# external_strip_v1.net
KiCad netlist of a schematic drawn in EAGLE
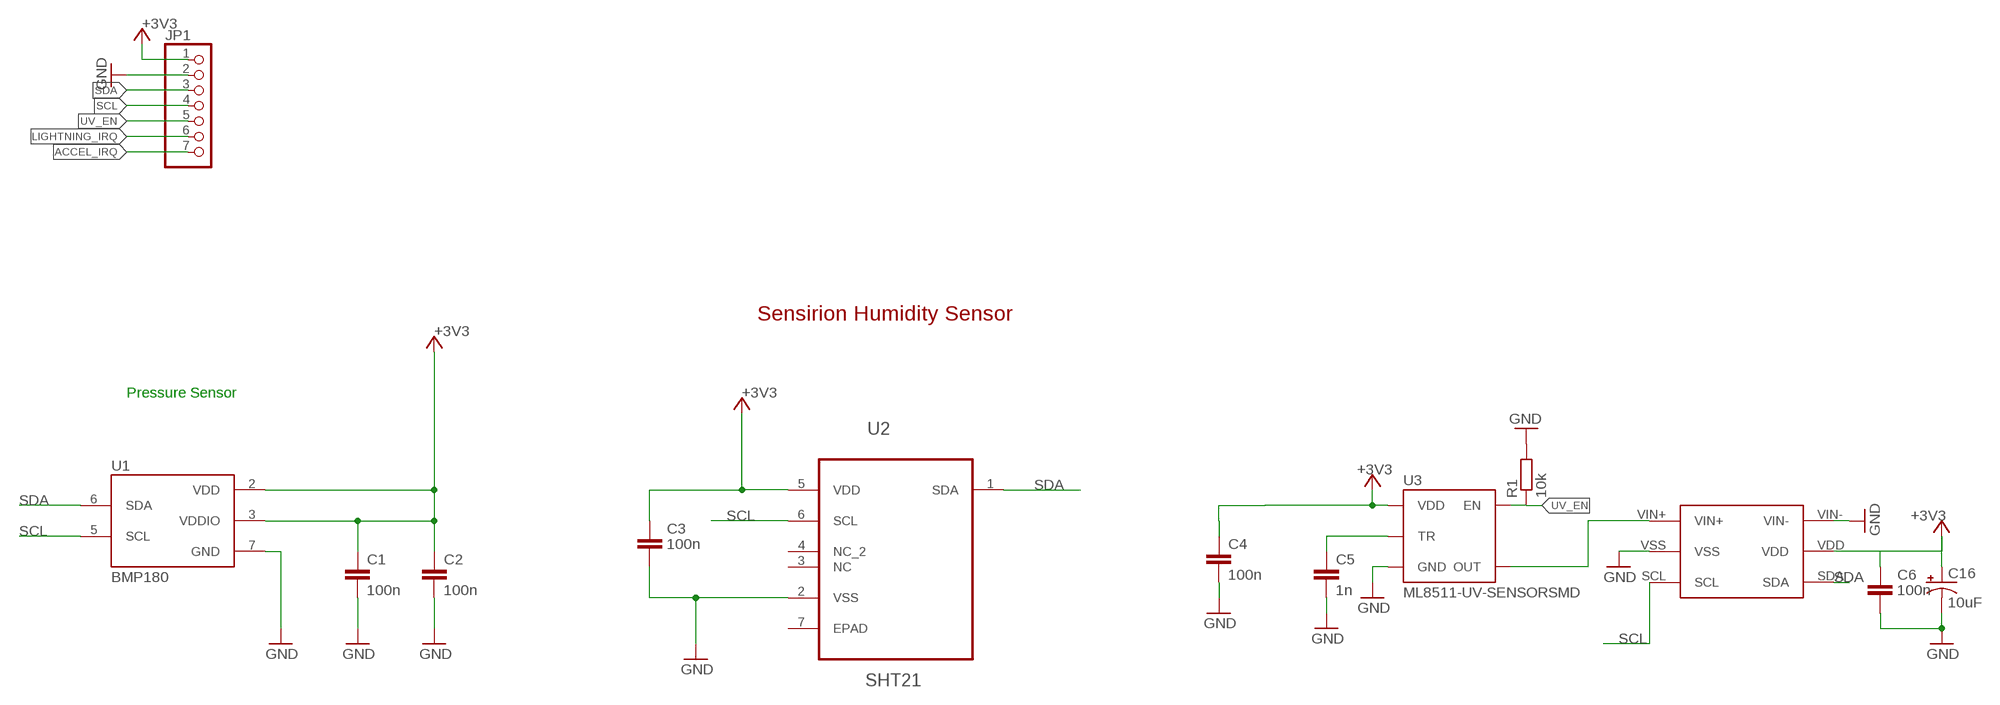
[diagram p0: schematic, sheet 1, part 1 of 2]
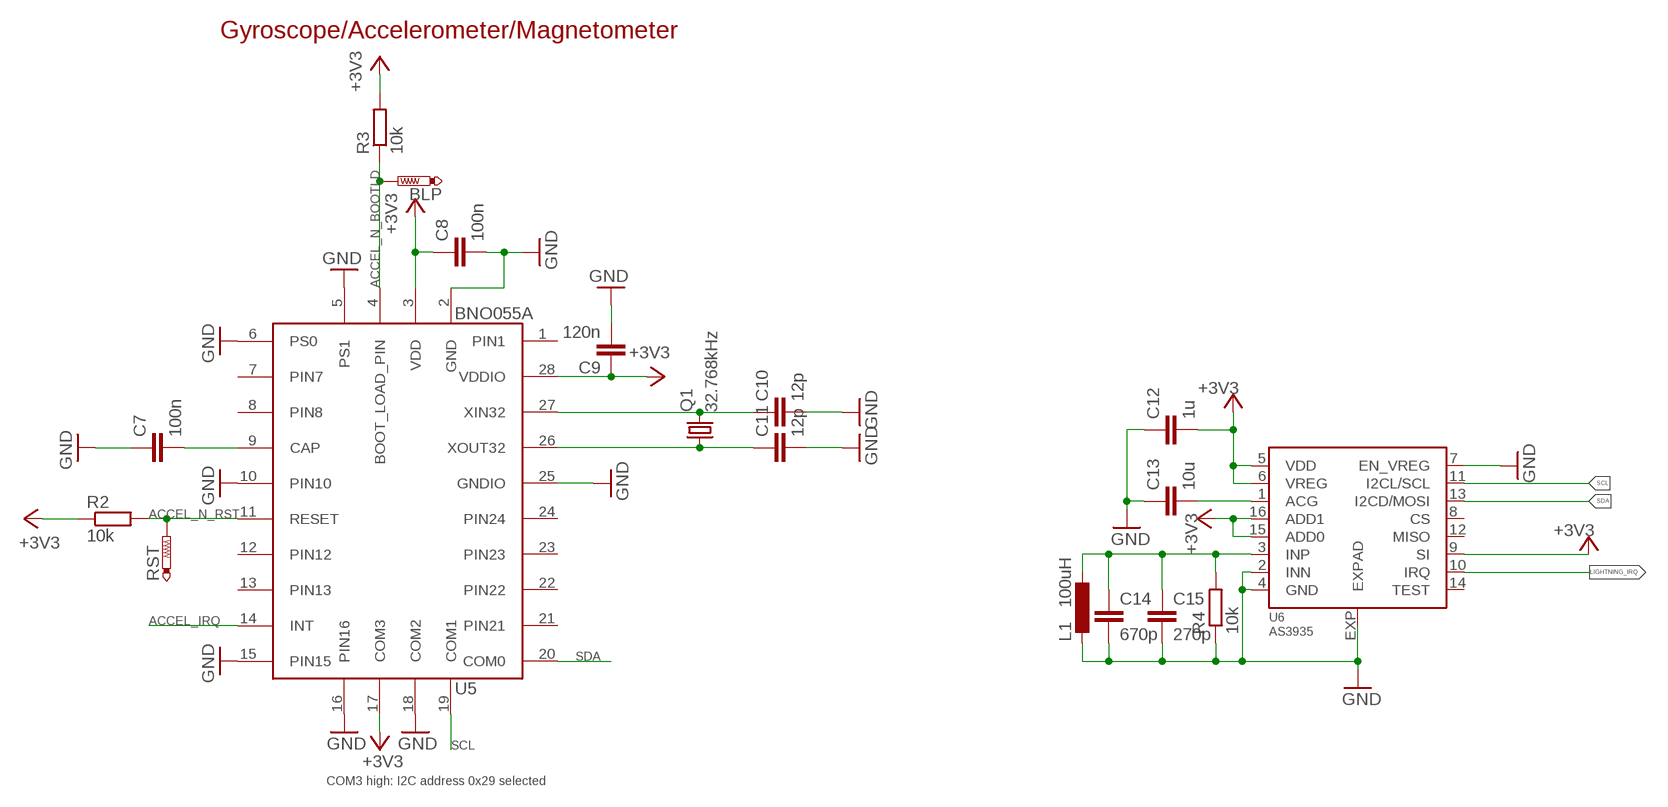
[diagram p1: schematic, sheet 1, part 2 of 2]

(export (version "E")
  (design (tool "Eeschema 10.0.6"))
  (components
    (comp (ref "BLP")
      (value "PTR1B1,27")
      (footprint "eagle-import:B1,27")
      (libsource (lib "eagle-import") (part "PTR1B1,27"))
    )
    (comp (ref "C1")
      (value "100n")
      (footprint "eagle-import:C0603")
      (libsource (lib "eagle-import") (part "C-EUC0603"))
    )
    (comp (ref "C2")
      (value "100n")
      (footprint "eagle-import:C0603")
      (libsource (lib "eagle-import") (part "C-EUC0603"))
    )
    (comp (ref "C3")
      (value "100n")
      (footprint "eagle-import:C0603")
      (libsource (lib "eagle-import") (part "C-EUC0603"))
    )
    (comp (ref "C4")
      (value "100n")
      (footprint "eagle-import:0603-CAP")
      (libsource (lib "eagle-import") (part "0.1UF-25V(+80/-20%)(0603)"))
    )
    (comp (ref "C5")
      (value "1n")
      (footprint "eagle-import:0603-CAP")
      (libsource (lib "eagle-import") (part "1NF/1000PF-50V-10%(0603)"))
    )
    (comp (ref "C6")
      (value "100n")
      (footprint "eagle-import:C0603")
      (libsource (lib "eagle-import") (part "C-EUC0603"))
    )
    (comp (ref "C7")
      (value "100n")
      (footprint "eagle-import:C0603")
      (libsource (lib "eagle-import") (part "C-EUC0603"))
    )
    (comp (ref "C8")
      (value "100n")
      (footprint "eagle-import:C0603")
      (libsource (lib "eagle-import") (part "C-EUC0603"))
    )
    (comp (ref "C9")
      (value "120n")
      (footprint "eagle-import:C0603")
      (libsource (lib "eagle-import") (part "C-EUC0603"))
    )
    (comp (ref "C10")
      (value "12p")
      (footprint "eagle-import:C0603")
      (libsource (lib "eagle-import") (part "C-EUC0603"))
    )
    (comp (ref "C11")
      (value "12p")
      (footprint "eagle-import:C0603")
      (libsource (lib "eagle-import") (part "C-EUC0603"))
    )
    (comp (ref "C12")
      (value "1u")
      (footprint "eagle-import:C0603")
      (libsource (lib "eagle-import") (part "C-EUC0603"))
    )
    (comp (ref "C13")
      (value "10u")
      (footprint "eagle-import:C0603")
      (libsource (lib "eagle-import") (part "C-EUC0603"))
    )
    (comp (ref "C14")
      (value "670p")
      (footprint "eagle-import:C0603")
      (libsource (lib "eagle-import") (part "C-EUC0603"))
    )
    (comp (ref "C15")
      (value "270p")
      (footprint "eagle-import:C0603")
      (libsource (lib "eagle-import") (part "C-EUC0603"))
    )
    (comp (ref "C16")
      (value "10uF")
      (footprint "eagle-import:EIA3216")
      (libsource (lib "eagle-import") (part "10UF-TANT"))
    )
    (comp (ref "JP1")
      (value "PINHD-1X7")
      (footprint "eagle-import:1X07")
      (libsource (lib "eagle-import") (part "PINHD-1X7"))
    )
    (comp (ref "L1")
      (value "100uH")
      (footprint "eagle-import:COILCRAFT")
      (libsource (lib "eagle-import") (part "COILCRAFT"))
    )
    (comp (ref "Q1")
      (value "32.768kHz")
      (footprint "eagle-import:FC-12M")
      (libsource (lib "eagle-import") (part "FC-12M"))
    )
    (comp (ref "R1")
      (value "10k")
      (footprint "eagle-import:R0603")
      (libsource (lib "eagle-import") (part "resistor_R-EU_R0603"))
    )
    (comp (ref "R2")
      (value "10k")
      (footprint "eagle-import:R0603")
      (libsource (lib "eagle-import") (part "R-EU_R0603"))
    )
    (comp (ref "R3")
      (value "10k")
      (footprint "eagle-import:R0603")
      (libsource (lib "eagle-import") (part "R-EU_R0603"))
    )
    (comp (ref "R4")
      (value "10k")
      (footprint "eagle-import:R0603")
      (libsource (lib "eagle-import") (part "resistor_R-EU_R0603"))
    )
    (comp (ref "RST")
      (value "PTR1B1,27")
      (footprint "eagle-import:B1,27")
      (libsource (lib "eagle-import") (part "PTR1B1,27"))
    )
    (comp (ref "U1")
      (value "BMP180")
      (footprint "eagle-import:BMP180")
      (libsource (lib "eagle-import") (part "BMP180"))
    )
    (comp (ref "U2")
      (value "SHT21")
      (footprint "eagle-import:DFN300X300X110-7N")
      (libsource (lib "eagle-import") (part "SHT21"))
    )
    (comp (ref "U3")
      (value "ML8511-UV-SENSORSMD")
      (footprint "eagle-import:ML8511")
      (libsource (lib "eagle-import") (part "ML8511-UV-SENSORSMD"))
    )
    (comp (ref "U4")
      (value "MCP3425")
      (footprint "eagle-import:SOT-23-6")
      (libsource (lib "eagle-import") (part "MCP3425"))
    )
    (comp (ref "U5")
      (value "BNO055A")
      (footprint "eagle-import:BNO055")
      (libsource (lib "eagle-import") (part "BNO055A"))
    )
    (comp (ref "U6")
      (value "AS3935")
      (footprint "eagle-import:16LDMLPQ")
      (libsource (lib "eagle-import") (part "AS3935"))
    )
  )
  (nets
    (net (code "1") (name "+3V3") (class "Default")
      (node (ref "C1") (pin "1") (pinfunction "1_1") (pintype "passive"))
      (node (ref "C12") (pin "2") (pinfunction "2_2") (pintype "passive"))
      (node (ref "C16") (pin "A") (pinfunction "+_A") (pintype "passive"))
      (node (ref "C2") (pin "1") (pinfunction "1_1") (pintype "passive"))
      (node (ref "C3") (pin "1") (pinfunction "1_1") (pintype "passive"))
      (node (ref "C4") (pin "1") (pinfunction "1_1") (pintype "passive"))
      (node (ref "C6") (pin "1") (pinfunction "1_1") (pintype "passive"))
      (node (ref "C8") (pin "1") (pinfunction "1_1") (pintype "passive"))
      (node (ref "C9") (pin "1") (pinfunction "1_1") (pintype "passive"))
      (node (ref "JP1") (pin "1") (pinfunction "1_1") (pintype "passive"))
      (node (ref "R2") (pin "1") (pinfunction "1_1") (pintype "passive"))
      (node (ref "R3") (pin "2") (pinfunction "2_2") (pintype "passive"))
      (node (ref "U1") (pin "2") (pinfunction "VDD_2") (pintype "power_in"))
      (node (ref "U1") (pin "3") (pinfunction "VDDIO_3") (pintype "power_in"))
      (node (ref "U2") (pin "5") (pinfunction "VDD_5") (pintype "power_in"))
      (node (ref "U3") (pin "7") (pinfunction "VDD_7") (pintype "power_in"))
      (node (ref "U4") (pin "VDD") (pinfunction "VDD_VDD") (pintype "bidirectional"))
      (node (ref "U5") (pin "17") (pinfunction "COM3_17") (pintype "bidirectional"))
      (node (ref "U5") (pin "28") (pinfunction "VDDIO_28") (pintype "bidirectional"))
      (node (ref "U5") (pin "3") (pinfunction "VDD_3") (pintype "bidirectional"))
      (node (ref "U6") (pin "15") (pinfunction "ADD0_15") (pintype "bidirectional"))
      (node (ref "U6") (pin "16") (pinfunction "ADD1_16") (pintype "bidirectional"))
      (node (ref "U6") (pin "5") (pinfunction "VDD_5") (pintype "bidirectional"))
      (node (ref "U6") (pin "6") (pinfunction "VREG_6") (pintype "bidirectional"))
      (node (ref "U6") (pin "9") (pinfunction "SI_9") (pintype "bidirectional"))
    )
    (net (code "2") (name "/ACCEL_N_BOOTLD") (class "Default")
      (node (ref "BLP") (pin "TP") (pinfunction "TP_TP") (pintype "input"))
      (node (ref "R3") (pin "1") (pinfunction "1_1") (pintype "passive"))
      (node (ref "U5") (pin "4") (pinfunction "BOOT_LOAD_PIN_4") (pintype "bidirectional"))
    )
    (net (code "3") (name "/ACCEL_N_RST") (class "Default")
      (node (ref "R2") (pin "2") (pinfunction "2_2") (pintype "passive"))
      (node (ref "RST") (pin "TP") (pinfunction "TP_TP") (pintype "input"))
      (node (ref "U5") (pin "11") (pinfunction "RESET_11") (pintype "bidirectional"))
    )
    (net (code "4") (name "ACCEL_IRQ") (class "Default")
      (node (ref "JP1") (pin "7") (pinfunction "7_7") (pintype "passive"))
      (node (ref "U5") (pin "14") (pinfunction "INT_14") (pintype "bidirectional"))
    )
    (net (code "5") (name "GND") (class "Default")
      (node (ref "C1") (pin "2") (pinfunction "2_2") (pintype "passive"))
      (node (ref "C10") (pin "2") (pinfunction "2_2") (pintype "passive"))
      (node (ref "C11") (pin "2") (pinfunction "2_2") (pintype "passive"))
      (node (ref "C12") (pin "1") (pinfunction "1_1") (pintype "passive"))
      (node (ref "C13") (pin "1") (pinfunction "1_1") (pintype "passive"))
      (node (ref "C14") (pin "2") (pinfunction "2_2") (pintype "passive"))
      (node (ref "C15") (pin "2") (pinfunction "2_2") (pintype "passive"))
      (node (ref "C16") (pin "C") (pinfunction "-_C") (pintype "passive"))
      (node (ref "C2") (pin "2") (pinfunction "2_2") (pintype "passive"))
      (node (ref "C3") (pin "2") (pinfunction "2_2") (pintype "passive"))
      (node (ref "C4") (pin "2") (pinfunction "2_2") (pintype "passive"))
      (node (ref "C5") (pin "2") (pinfunction "2_2") (pintype "passive"))
      (node (ref "C6") (pin "2") (pinfunction "2_2") (pintype "passive"))
      (node (ref "C7") (pin "1") (pinfunction "1_1") (pintype "passive"))
      (node (ref "C8") (pin "2") (pinfunction "2_2") (pintype "passive"))
      (node (ref "C9") (pin "2") (pinfunction "2_2") (pintype "passive"))
      (node (ref "JP1") (pin "2") (pinfunction "2_2") (pintype "passive"))
      (node (ref "L1") (pin "2") (pinfunction "2_2") (pintype "passive"))
      (node (ref "R1") (pin "2") (pinfunction "2_2") (pintype "passive"))
      (node (ref "R4") (pin "1") (pinfunction "1_1") (pintype "passive"))
      (node (ref "U1") (pin "7") (pinfunction "GND_7") (pintype "power_in"))
      (node (ref "U2") (pin "2") (pinfunction "VSS_2") (pintype "power_in"))
      (node (ref "U3") (pin "5") (pinfunction "GND_5") (pintype "power_in"))
      (node (ref "U4") (pin "VIN-") (pinfunction "VIN-_VIN-") (pintype "bidirectional"))
      (node (ref "U4") (pin "VSS") (pinfunction "VSS_VSS") (pintype "bidirectional"))
      (node (ref "U5") (pin "10") (pinfunction "PIN10_10") (pintype "bidirectional"))
      (node (ref "U5") (pin "15") (pinfunction "PIN15_15") (pintype "bidirectional"))
      (node (ref "U5") (pin "16") (pinfunction "PIN16_16") (pintype "bidirectional"))
      (node (ref "U5") (pin "18") (pinfunction "COM2_18") (pintype "bidirectional"))
      (node (ref "U5") (pin "2") (pinfunction "GND_2") (pintype "bidirectional"))
      (node (ref "U5") (pin "25") (pinfunction "GNDIO_25") (pintype "bidirectional"))
      (node (ref "U5") (pin "5") (pinfunction "PS1_5") (pintype "bidirectional"))
      (node (ref "U5") (pin "6") (pinfunction "PS0_6") (pintype "bidirectional"))
      (node (ref "U6") (pin "2") (pinfunction "INN_2") (pintype "bidirectional"))
      (node (ref "U6") (pin "4") (pinfunction "GND_4") (pintype "bidirectional"))
      (node (ref "U6") (pin "7") (pinfunction "EN_VREG_7") (pintype "bidirectional"))
      (node (ref "U6") (pin "EXP") (pinfunction "EXPAD_EXP") (pintype "bidirectional"))
    )
    (net (code "6") (name "LIGHTNING_IRQ") (class "Default")
      (node (ref "JP1") (pin "6") (pinfunction "6_6") (pintype "passive"))
      (node (ref "U6") (pin "10") (pinfunction "IRQ_10") (pintype "bidirectional"))
    )
    (net (code "7") (name "Net-(U3-OUT)") (class "Default")
      (node (ref "U3") (pin "8") (pinfunction "OUT_8") (pintype "output"))
      (node (ref "U4") (pin "VIN+") (pinfunction "VIN+_VIN+") (pintype "bidirectional"))
    )
    (net (code "8") (name "Net-(U3-TR)") (class "Default")
      (node (ref "C5") (pin "1") (pinfunction "1_1") (pintype "passive"))
      (node (ref "U3") (pin "10") (pinfunction "TR_10") (pintype "power_in"))
    )
    (net (code "9") (name "Net-(U5-CAP)") (class "Default")
      (node (ref "C7") (pin "2") (pinfunction "2_2") (pintype "passive"))
      (node (ref "U5") (pin "9") (pinfunction "CAP_9") (pintype "bidirectional"))
    )
    (net (code "10") (name "Net-(U5-XIN32)") (class "Default")
      (node (ref "C10") (pin "1") (pinfunction "1_1") (pintype "passive"))
      (node (ref "Q1") (pin "2") (pinfunction "2_2") (pintype "passive"))
      (node (ref "U5") (pin "27") (pinfunction "XIN32_27") (pintype "bidirectional"))
    )
    (net (code "11") (name "Net-(U5-XOUT32)") (class "Default")
      (node (ref "C11") (pin "1") (pinfunction "1_1") (pintype "passive"))
      (node (ref "Q1") (pin "1") (pinfunction "1_1") (pintype "passive"))
      (node (ref "U5") (pin "26") (pinfunction "XOUT32_26") (pintype "bidirectional"))
    )
    (net (code "12") (name "Net-(U6-ACG)") (class "Default")
      (node (ref "C13") (pin "2") (pinfunction "2_2") (pintype "passive"))
      (node (ref "U6") (pin "1") (pinfunction "ACG_1") (pintype "bidirectional"))
    )
    (net (code "13") (name "Net-(U6-INP)") (class "Default")
      (node (ref "C14") (pin "1") (pinfunction "1_1") (pintype "passive"))
      (node (ref "C15") (pin "1") (pinfunction "1_1") (pintype "passive"))
      (node (ref "L1") (pin "1") (pinfunction "1_1") (pintype "passive"))
      (node (ref "R4") (pin "2") (pinfunction "2_2") (pintype "passive"))
      (node (ref "U6") (pin "3") (pinfunction "INP_3") (pintype "bidirectional"))
    )
    (net (code "14") (name "SCL") (class "Default")
      (node (ref "JP1") (pin "4") (pinfunction "4_4") (pintype "passive"))
      (node (ref "U1") (pin "5") (pinfunction "SCL_5") (pintype "input"))
      (node (ref "U2") (pin "6") (pinfunction "SCL_6") (pintype "input"))
      (node (ref "U4") (pin "SCL") (pinfunction "SCL_SCL") (pintype "bidirectional"))
      (node (ref "U5") (pin "19") (pinfunction "COM1_19") (pintype "bidirectional"))
      (node (ref "U6") (pin "11") (pinfunction "I2CL/SCL_11") (pintype "bidirectional"))
    )
    (net (code "15") (name "SDA") (class "Default")
      (node (ref "JP1") (pin "3") (pinfunction "3_3") (pintype "passive"))
      (node (ref "U1") (pin "6") (pinfunction "SDA_6") (pintype "bidirectional"))
      (node (ref "U2") (pin "1") (pinfunction "SDA_1") (pintype "bidirectional"))
      (node (ref "U4") (pin "SDA") (pinfunction "SDA_SDA") (pintype "bidirectional"))
      (node (ref "U5") (pin "20") (pinfunction "COM0_20") (pintype "bidirectional"))
      (node (ref "U6") (pin "13") (pinfunction "I2CD/MOSI_13") (pintype "bidirectional"))
    )
    (net (code "16") (name "UV_EN") (class "Default")
      (node (ref "JP1") (pin "5") (pinfunction "5_5") (pintype "passive"))
      (node (ref "R1") (pin "1") (pinfunction "1_1") (pintype "passive"))
      (node (ref "U3") (pin "4") (pinfunction "EN_4") (pintype "input"))
    )
    (net (code "17") (name "unconnected-(U2-EPAD-Pad7)") (class "Default")
      (node (ref "U2") (pin "7") (pinfunction "EPAD_7") (pintype "passive"))
    )
    (net (code "18") (name "unconnected-(U2-NC-Pad3)") (class "Default")
      (node (ref "U2") (pin "3") (pinfunction "NC_3") (pintype "no_connect"))
    )
    (net (code "19") (name "unconnected-(U2-NC_2-Pad4)") (class "Default")
      (node (ref "U2") (pin "4") (pinfunction "NC_2_4") (pintype "no_connect"))
    )
    (net (code "20") (name "unconnected-(U5-PIN1-Pad1)") (class "Default")
      (node (ref "U5") (pin "1") (pinfunction "PIN1_1") (pintype "bidirectional"))
    )
    (net (code "21") (name "unconnected-(U5-PIN7-Pad7)") (class "Default")
      (node (ref "U5") (pin "7") (pinfunction "PIN7_7") (pintype "bidirectional"))
    )
    (net (code "22") (name "unconnected-(U5-PIN8-Pad8)") (class "Default")
      (node (ref "U5") (pin "8") (pinfunction "PIN8_8") (pintype "bidirectional"))
    )
    (net (code "23") (name "unconnected-(U5-PIN12-Pad12)") (class "Default")
      (node (ref "U5") (pin "12") (pinfunction "PIN12_12") (pintype "bidirectional"))
    )
    (net (code "24") (name "unconnected-(U5-PIN13-Pad13)") (class "Default")
      (node (ref "U5") (pin "13") (pinfunction "PIN13_13") (pintype "bidirectional"))
    )
    (net (code "25") (name "unconnected-(U5-PIN21-Pad21)") (class "Default")
      (node (ref "U5") (pin "21") (pinfunction "PIN21_21") (pintype "bidirectional"))
    )
    (net (code "26") (name "unconnected-(U5-PIN22-Pad22)") (class "Default")
      (node (ref "U5") (pin "22") (pinfunction "PIN22_22") (pintype "bidirectional"))
    )
    (net (code "27") (name "unconnected-(U5-PIN23-Pad23)") (class "Default")
      (node (ref "U5") (pin "23") (pinfunction "PIN23_23") (pintype "bidirectional"))
    )
    (net (code "28") (name "unconnected-(U5-PIN24-Pad24)") (class "Default")
      (node (ref "U5") (pin "24") (pinfunction "PIN24_24") (pintype "bidirectional"))
    )
    (net (code "29") (name "unconnected-(U6-CS-Pad8)") (class "Default")
      (node (ref "U6") (pin "8") (pinfunction "CS_8") (pintype "bidirectional"))
    )
    (net (code "30") (name "unconnected-(U6-MISO-Pad12)") (class "Default")
      (node (ref "U6") (pin "12") (pinfunction "MISO_12") (pintype "bidirectional"))
    )
    (net (code "31") (name "unconnected-(U6-TEST-Pad14)") (class "Default")
      (node (ref "U6") (pin "14") (pinfunction "TEST_14") (pintype "passive"))
    )
  )
)
